# 1-Schematic_Race_project_receiver.net
KiCad netlist of a schematic drawn in EasyEDA
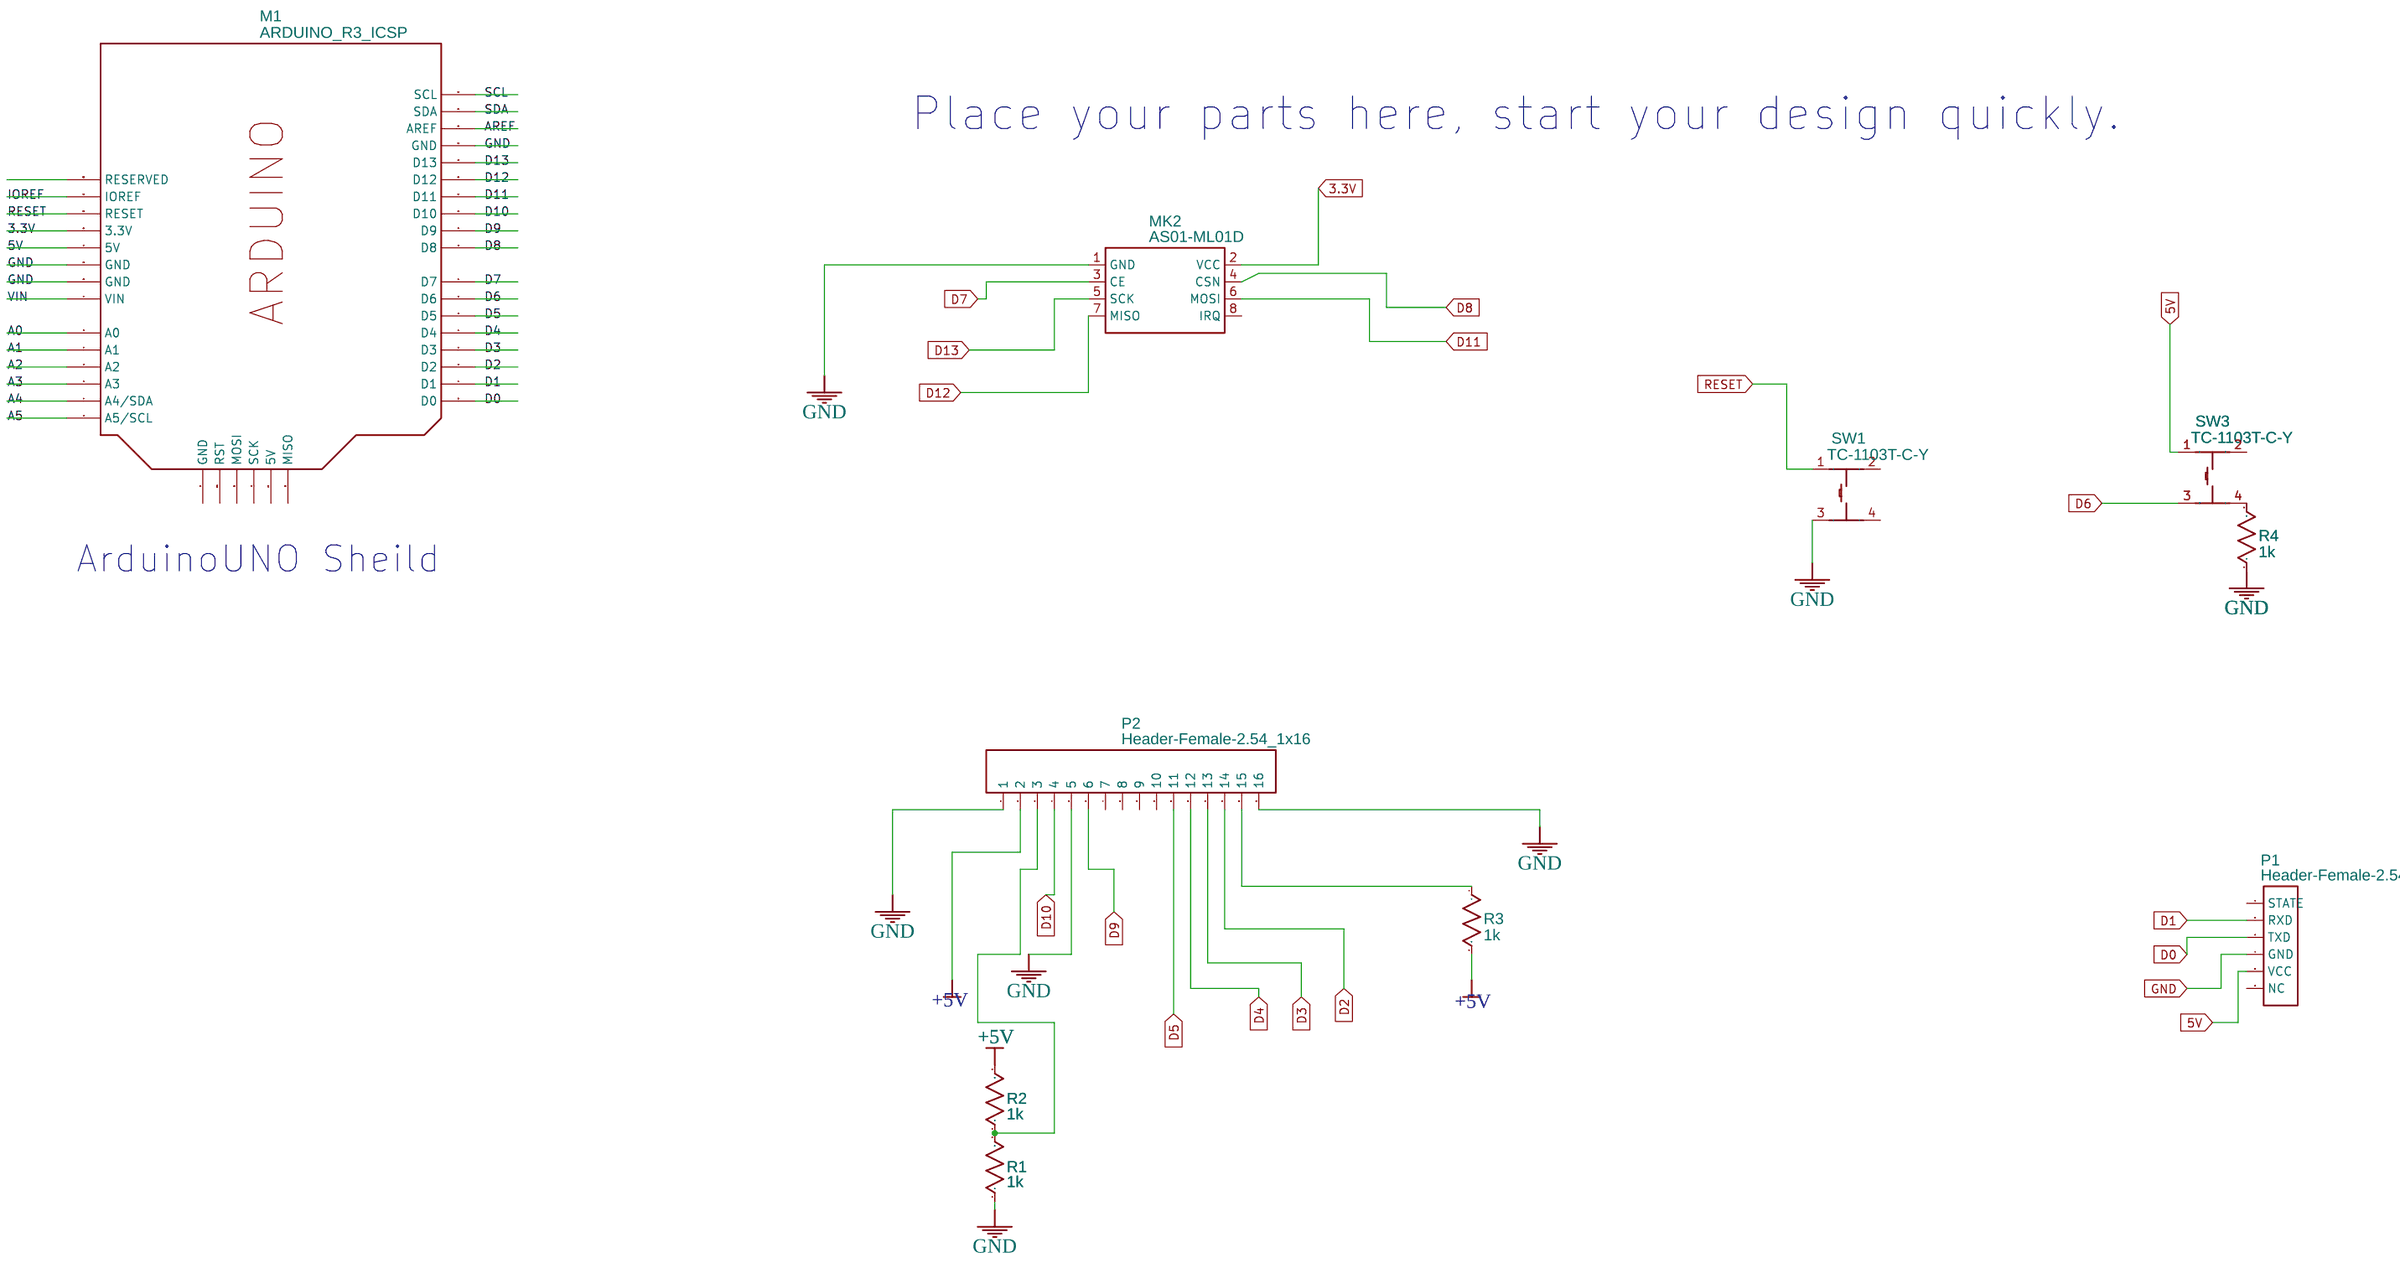
[diagram p0: schematic sheet]

(export (version "E")
  (design (tool "Eeschema 10.0.6"))
  (components
    (comp (ref "M1")
      (value "ARDUINO_R3_ICSP")
      (fields (field (name "BOM_Manufacturer Part") "?"))
      (libsource (lib "") (part "Unknown_70_-10"))
    )
    (comp (ref "MK2")
      (value "AS01-ML01D")
      (fields (field (name "BOM_Supplier Part") "C84803"))
      (libsource (lib "") (part "Unknown_695_135"))
    )
    (comp (ref "P1")
      (value "Header-Female-2.54_1x6")
      (fields
        (field (name "BOM_Manufacturer Part") "Female header 1*6p")
        (field (name "BOM_Supplier Part") "C40877")
      )
      (libsource (lib "") (part "Unknown_1345_520"))
    )
    (comp (ref "P2")
      (value "Header-Female-2.54_1x16")
      (fields
        (field (name "BOM_Manufacturer Part") "Female header1*16P pitch 2.54mm")
        (field (name "BOM_Supplier Part") "C66987")
      )
      (libsource (lib "") (part "Unknown_675_420"))
    )
    (comp (ref "R1")
      (value "1k")
      (fields (field (name "BOM_Manufacturer Part") "?"))
      (libsource (lib "") (part "Res_AXIAL-0.3(1/8W)_US"))
    )
    (comp (ref "R2")
      (value "1k")
      (fields (field (name "BOM_Manufacturer Part") "?"))
      (libsource (lib "") (part "Res_AXIAL-0.3(1/8W)_US"))
    )
    (comp (ref "R3")
      (value "1k")
      (fields (field (name "BOM_Manufacturer Part") "?"))
      (libsource (lib "") (part "Res_AXIAL-0.3(1/8W)_US_1"))
    )
    (comp (ref "R4")
      (value "1k")
      (fields (field (name "BOM_Manufacturer Part") "?"))
      (libsource (lib "") (part "Res_AXIAL-0.3(1/8W)_US"))
    )
    (comp (ref "SW1")
      (value "TC-1103T-C-Y")
      (fields (field (name "BOM_Supplier Part") "C318966"))
      (libsource (lib "") (part "Unknown_1095_260"))
    )
    (comp (ref "SW3")
      (value "TC-1103T-C-Y")
      (fields (field (name "BOM_Supplier Part") "C318966"))
      (libsource (lib "") (part "Unknown_1310_250"))
    )
  )
  (nets
    (net (code "1") (name "+5V") (class "Default")
      (node (ref "P2") (pin "2") (pinfunction "2_2") (pintype "input"))
      (node (ref "R2") (pin "2") (pinfunction "2_2") (pintype "unspecified"))
      (node (ref "R3") (pin "2") (pinfunction "2_2") (pintype "unspecified"))
    )
    (net (code "2") (name "/A0") (class "Default")
      (node (ref "M1") (pin "A0") (pinfunction "A0_A0") (pintype "unspecified"))
    )
    (net (code "3") (name "/A1") (class "Default")
      (node (ref "M1") (pin "A1") (pinfunction "A1_A1") (pintype "unspecified"))
    )
    (net (code "4") (name "/A2") (class "Default")
      (node (ref "M1") (pin "A2") (pinfunction "A2_A2") (pintype "unspecified"))
    )
    (net (code "5") (name "/A3") (class "Default")
      (node (ref "M1") (pin "A3") (pinfunction "A3_A3") (pintype "unspecified"))
    )
    (net (code "6") (name "/A4") (class "Default")
      (node (ref "M1") (pin "A4") (pinfunction "A4/SDA_A4") (pintype "unspecified"))
    )
    (net (code "7") (name "/A5") (class "Default")
      (node (ref "M1") (pin "A5") (pinfunction "A5/SCL_A5") (pintype "unspecified"))
    )
    (net (code "8") (name "/AREF") (class "Default")
      (node (ref "M1") (pin "AREF") (pinfunction "AREF_AREF") (pintype "unspecified"))
    )
    (net (code "9") (name "/IOREF") (class "Default")
      (node (ref "M1") (pin "IOREF") (pinfunction "IOREF_IOREF") (pintype "output"))
    )
    (net (code "10") (name "/SCL") (class "Default")
      (node (ref "M1") (pin "SCL") (pinfunction "SCL_SCL") (pintype "unspecified"))
    )
    (net (code "11") (name "/SDA") (class "Default")
      (node (ref "M1") (pin "SDA") (pinfunction "SDA_SDA") (pintype "unspecified"))
    )
    (net (code "12") (name "/VIN") (class "Default")
      (node (ref "M1") (pin "VIN") (pinfunction "VIN_VIN") (pintype "passive"))
    )
    (net (code "13") (name "3.3V") (class "Default")
      (node (ref "M1") (pin "3.3V") (pinfunction "3.3V_3.3V") (pintype "passive"))
      (node (ref "MK2") (pin "2") (pinfunction "VCC_2") (pintype "unspecified"))
    )
    (net (code "14") (name "5V") (class "Default")
      (node (ref "M1") (pin "5V") (pinfunction "5V_5V") (pintype "passive"))
      (node (ref "P1") (pin "5") (pinfunction "VCC_5") (pintype "input"))
      (node (ref "SW3") (pin "1") (pinfunction "1_1") (pintype "unspecified"))
    )
    (net (code "15") (name "D0") (class "Default")
      (node (ref "M1") (pin "D0") (pinfunction "D0_D0") (pintype "unspecified"))
      (node (ref "P1") (pin "3") (pinfunction "TXD_3") (pintype "input"))
    )
    (net (code "16") (name "D1") (class "Default")
      (node (ref "M1") (pin "D1") (pinfunction "D1_D1") (pintype "unspecified"))
      (node (ref "P1") (pin "2") (pinfunction "RXD_2") (pintype "input"))
    )
    (net (code "17") (name "D2") (class "Default")
      (node (ref "M1") (pin "D2") (pinfunction "D2_D2") (pintype "unspecified"))
      (node (ref "P2") (pin "14") (pinfunction "14_14") (pintype "input"))
    )
    (net (code "18") (name "D3") (class "Default")
      (node (ref "M1") (pin "D3") (pinfunction "D3_D3") (pintype "unspecified"))
      (node (ref "P2") (pin "13") (pinfunction "13_13") (pintype "input"))
    )
    (net (code "19") (name "D4") (class "Default")
      (node (ref "M1") (pin "D4") (pinfunction "D4_D4") (pintype "unspecified"))
      (node (ref "P2") (pin "12") (pinfunction "12_12") (pintype "input"))
    )
    (net (code "20") (name "D5") (class "Default")
      (node (ref "M1") (pin "D5") (pinfunction "D5_D5") (pintype "unspecified"))
      (node (ref "P2") (pin "11") (pinfunction "11_11") (pintype "input"))
    )
    (net (code "21") (name "D6") (class "Default")
      (node (ref "M1") (pin "D6") (pinfunction "D6_D6") (pintype "unspecified"))
      (node (ref "SW3") (pin "3") (pinfunction "3_3") (pintype "unspecified"))
    )
    (net (code "22") (name "D7") (class "Default")
      (node (ref "M1") (pin "D7") (pinfunction "D7_D7") (pintype "unspecified"))
      (node (ref "MK2") (pin "3") (pinfunction "CE_3") (pintype "unspecified"))
    )
    (net (code "23") (name "D8") (class "Default")
      (node (ref "M1") (pin "D8") (pinfunction "D8_D8") (pintype "unspecified"))
      (node (ref "MK2") (pin "4") (pinfunction "CSN_4") (pintype "unspecified"))
    )
    (net (code "24") (name "D9") (class "Default")
      (node (ref "M1") (pin "D9") (pinfunction "D9_D9") (pintype "unspecified"))
      (node (ref "P2") (pin "6") (pinfunction "6_6") (pintype "input"))
    )
    (net (code "25") (name "D10") (class "Default")
      (node (ref "M1") (pin "D10") (pinfunction "D10_D10") (pintype "unspecified"))
      (node (ref "P2") (pin "4") (pinfunction "4_4") (pintype "input"))
    )
    (net (code "26") (name "D11") (class "Default")
      (node (ref "M1") (pin "D11") (pinfunction "D11_D11") (pintype "unspecified"))
      (node (ref "MK2") (pin "6") (pinfunction "MOSI_6") (pintype "unspecified"))
    )
    (net (code "27") (name "D12") (class "Default")
      (node (ref "M1") (pin "D12") (pinfunction "D12_D12") (pintype "unspecified"))
      (node (ref "MK2") (pin "7") (pinfunction "MISO_7") (pintype "unspecified"))
    )
    (net (code "28") (name "D13") (class "Default")
      (node (ref "M1") (pin "D13") (pinfunction "D13_D13") (pintype "unspecified"))
      (node (ref "MK2") (pin "5") (pinfunction "SCK_5") (pintype "unspecified"))
    )
    (net (code "29") (name "GND") (class "Default")
      (node (ref "M1") (pin "GND") (pinfunction "GND_GND") (pintype "passive"))
      (node (ref "MK2") (pin "1") (pinfunction "GND_1") (pintype "unspecified"))
      (node (ref "P1") (pin "4") (pinfunction "GND_4") (pintype "input"))
      (node (ref "P2") (pin "1") (pinfunction "1_1") (pintype "input"))
      (node (ref "P2") (pin "16") (pinfunction "16_16") (pintype "input"))
      (node (ref "P2") (pin "5") (pinfunction "5_5") (pintype "input"))
      (node (ref "R1") (pin "1") (pinfunction "1_1") (pintype "unspecified"))
      (node (ref "R4") (pin "1") (pinfunction "1_1") (pintype "unspecified"))
      (node (ref "SW1") (pin "3") (pinfunction "3_3") (pintype "unspecified"))
    )
    (net (code "30") (name "Net-(P2-Pad3)") (class "Default")
      (node (ref "P2") (pin "3") (pinfunction "3_3") (pintype "input"))
      (node (ref "R1") (pin "2") (pinfunction "2_2") (pintype "unspecified"))
      (node (ref "R2") (pin "1") (pinfunction "1_1") (pintype "unspecified"))
    )
    (net (code "31") (name "Net-(P2-Pad15)") (class "Default")
      (node (ref "P2") (pin "15") (pinfunction "15_15") (pintype "input"))
      (node (ref "R3") (pin "1") (pinfunction "1_1") (pintype "unspecified"))
    )
    (net (code "32") (name "Net-(R4-Pad2)") (class "Default")
      (node (ref "R4") (pin "2") (pinfunction "2_2") (pintype "unspecified"))
      (node (ref "SW3") (pin "4") (pinfunction "4_4") (pintype "unspecified"))
    )
    (net (code "33") (name "RESET") (class "Default")
      (node (ref "M1") (pin "RESET") (pinfunction "RESET_RESET") (pintype "unspecified"))
      (node (ref "SW1") (pin "1") (pinfunction "1_1") (pintype "unspecified"))
    )
    (net (code "34") (name "unconnected-(M1-5V-Pad5V_ICSP)") (class "Default")
      (node (ref "M1") (pin "5V_ICSP") (pinfunction "5V_5V_ICSP") (pintype "unspecified"))
    )
    (net (code "35") (name "unconnected-(M1-PadGND)") (class "Default")
      (node (ref "M1") (pin "GND") (pinfunction "GND_GND") (pintype "unspecified"))
    )
    (net (code "36") (name "unconnected-(M1-PadMISO)") (class "Default")
      (node (ref "M1") (pin "MISO") (pinfunction "MISO_MISO") (pintype "unspecified"))
    )
    (net (code "37") (name "unconnected-(M1-PadMOSI)") (class "Default")
      (node (ref "M1") (pin "MOSI") (pinfunction "MOSI_MOSI") (pintype "unspecified"))
    )
    (net (code "38") (name "unconnected-(M1-PadRESERVED)") (class "Default")
      (node (ref "M1") (pin "RESERVED") (pinfunction "RESERVED_RESERVED") (pintype "unspecified"))
    )
    (net (code "39") (name "unconnected-(M1-PadSCK)") (class "Default")
      (node (ref "M1") (pin "SCK") (pinfunction "SCK_SCK") (pintype "unspecified"))
    )
    (net (code "40") (name "unconnected-(M1-RST-PadRESET_ICSP)") (class "Default")
      (node (ref "M1") (pin "RESET_ICSP") (pinfunction "RST_RESET_ICSP") (pintype "unspecified"))
    )
    (net (code "41") (name "unconnected-(MK2-IRQ-Pad8)") (class "Default")
      (node (ref "MK2") (pin "8") (pinfunction "IRQ_8") (pintype "unspecified"))
    )
    (net (code "42") (name "unconnected-(P1-NC-Pad6)") (class "Default")
      (node (ref "P1") (pin "6") (pinfunction "NC_6") (pintype "input"))
    )
    (net (code "43") (name "unconnected-(P1-STATE-Pad1)") (class "Default")
      (node (ref "P1") (pin "1") (pinfunction "STATE_1") (pintype "input"))
    )
    (net (code "44") (name "unconnected-(P2-Pad7)") (class "Default")
      (node (ref "P2") (pin "7") (pinfunction "7_7") (pintype "input"))
    )
    (net (code "45") (name "unconnected-(P2-Pad8)") (class "Default")
      (node (ref "P2") (pin "8") (pinfunction "8_8") (pintype "input"))
    )
    (net (code "46") (name "unconnected-(P2-Pad9)") (class "Default")
      (node (ref "P2") (pin "9") (pinfunction "9_9") (pintype "input"))
    )
    (net (code "47") (name "unconnected-(P2-Pad10)") (class "Default")
      (node (ref "P2") (pin "10") (pinfunction "10_10") (pintype "input"))
    )
    (net (code "48") (name "unconnected-(SW1-Pad2)") (class "Default")
      (node (ref "SW1") (pin "2") (pinfunction "2_2") (pintype "unspecified"))
    )
    (net (code "49") (name "unconnected-(SW1-Pad4)") (class "Default")
      (node (ref "SW1") (pin "4") (pinfunction "4_4") (pintype "unspecified"))
    )
    (net (code "50") (name "unconnected-(SW3-Pad2)") (class "Default")
      (node (ref "SW3") (pin "2") (pinfunction "2_2") (pintype "unspecified"))
    )
  )
)
